# Eth-Crystal.net
KiCad netlist of a schematic drawn in Altium Designer
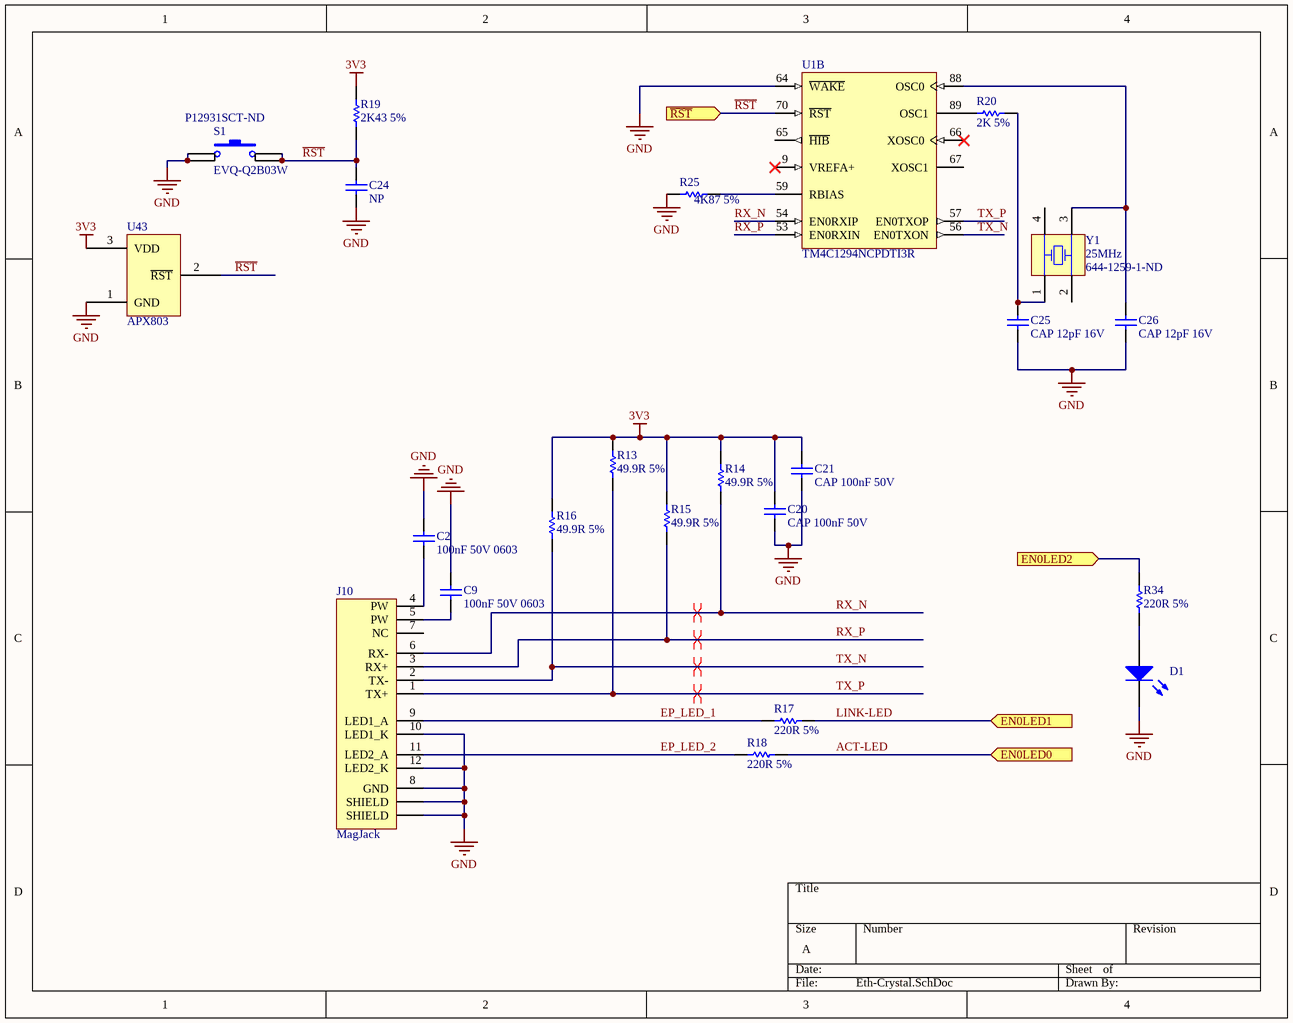
[diagram p0: Eth-Crystal.SchDoc]

(export (version "E")
  (design (tool "Eeschema 10.0.6"))
  (components
    (comp (ref "C2")
      (value "100nF 50V 0603")
      (footprint "CAPC0603(1608)100_M")
      (description "CAP 100nF 50V -20% to +80% 0603 (1608 Metric) Thickness 1mm SMD")
      (fields (field (name "TOLERANCE") "-20% to +80%"))
      (libsource (lib "Altium Content Vault") (part "CMP-1035-02594-1"))
    )
    (comp (ref "C9")
      (value "100nF 50V 0603")
      (footprint "CAPC0603(1608)100_M")
      (description "CAP 100nF 50V -20% to +80% 0603 (1608 Metric) Thickness 1mm SMD")
      (fields (field (name "TOLERANCE") "-20% to +80%"))
      (libsource (lib "Altium Content Vault") (part "CMP-1035-02594-1"))
    )
    (comp (ref "C20")
      (value "CAP 100nF 50V")
      (footprint "CAPC0603(1608)100_M")
      (description "CAP 100nF 50V Â±0.1pF 0603 (1608 Metric) Thickness 1mm SMD")
      (fields (field (name "TOLERANCE") "Â±0.1pF"))
      (libsource (lib "Altium Content Vault") (part "CMP-1035-00010-1"))
    )
    (comp (ref "C21")
      (value "CAP 100nF 50V")
      (footprint "CAPC0603(1608)100_M")
      (description "CAP 100nF 50V Â±0.1pF 0603 (1608 Metric) Thickness 1mm SMD")
      (fields (field (name "TOLERANCE") "Â±0.1pF"))
      (libsource (lib "Altium Content Vault") (part "CMP-1035-00010-1"))
    )
    (comp (ref "C24")
      (value "NP")
      (footprint "0603")
      (description "Capacitor (Semiconductor SIM Model)")
      (fields (field (name "PUBLISHER") "Altium Limited"))
      (libsource (lib "snarc+") (part "Cap_100pF"))
    )
    (comp (ref "C25")
      (value "CAP 12pF 16V")
      (footprint "CAPC0603(1608)100_L")
      (description "CAP 12pF 16V Â±0.25pF 0603 (1608 Metric) Thickness 1mm SMD")
      (fields (field (name "TOLERANCE") "Â±0.25pF"))
      (libsource (lib "Altium Content Vault") (part "CAP"))
    )
    (comp (ref "C26")
      (value "CAP 12pF 16V")
      (footprint "CAPC0603(1608)100_L")
      (description "CAP 12pF 16V Â±0.25pF 0603 (1608 Metric) Thickness 1mm SMD")
      (fields (field (name "TOLERANCE") "Â±0.25pF"))
      (libsource (lib "Altium Content Vault") (part "CAP"))
    )
    (comp (ref "D1")
      (value "LED")
      (footprint "LED-0603")
      (description "Typical RED, GREEN, YELLOW, AMBER GaAs LED")
      (fields (field (name "PUBLISHER") "Altium Limited"))
      (libsource (lib "HSBNE-Vend") (part "LED"))
    )
    (comp (ref "J10") (value "MagJack") (footprint "magjack") (libsource (lib "HSBNE-MAIN") (part "MagJack")))
    (comp (ref "R13")
      (value "49.9R 5%")
      (footprint "RESC0603(1608)_M")
      (description "49.9R 0.1W 5% 0603 (1608 Metric)  SMD")
      (fields (field (name "TOLERANCE") "5 %") (field (name "POWER") "0.1 W"))
      (libsource (lib "Altium Content Vault") (part "CMP-1012-00042-1"))
    )
    (comp (ref "R14")
      (value "49.9R 5%")
      (footprint "RESC0603(1608)_M")
      (description "49.9R 0.1W 5% 0603 (1608 Metric)  SMD")
      (fields (field (name "TOLERANCE") "5 %") (field (name "POWER") "0.1 W"))
      (libsource (lib "Altium Content Vault") (part "CMP-1012-00042-1"))
    )
    (comp (ref "R15")
      (value "49.9R 5%")
      (footprint "RESC0603(1608)_M")
      (description "49.9R 0.1W 5% 0603 (1608 Metric)  SMD")
      (fields (field (name "TOLERANCE") "5 %") (field (name "POWER") "0.1 W"))
      (libsource (lib "Altium Content Vault") (part "CMP-1012-00042-1"))
    )
    (comp (ref "R16")
      (value "49.9R 5%")
      (footprint "RESC0603(1608)_M")
      (description "49.9R 0.1W 5% 0603 (1608 Metric)  SMD")
      (fields (field (name "TOLERANCE") "5 %") (field (name "POWER") "0.1 W"))
      (libsource (lib "Altium Content Vault") (part "CMP-1012-00042-1"))
    )
    (comp (ref "R17")
      (value "220R 5%")
      (footprint "RESC0603(1608)_M")
      (description "220R 0.1W 5% 0603 (1608 Metric)  SMD")
      (fields (field (name "POWER") "0.1 W") (field (name "TOLERANCE") "5 %"))
      (libsource (lib "Altium Content Vault") (part "CMP-1012-00058-1"))
    )
    (comp (ref "R18")
      (value "220R 5%")
      (footprint "RESC0603(1608)_M")
      (description "220R 0.1W 5% 0603 (1608 Metric)  SMD")
      (fields (field (name "POWER") "0.1 W") (field (name "TOLERANCE") "5 %"))
      (libsource (lib "Altium Content Vault") (part "CMP-1012-00058-1"))
    )
    (comp (ref "R19")
      (value "2K43 5%")
      (footprint "RESC0603(1608)_M")
      (description "2K43 0.1W 5% 0603 (1608 Metric)  SMD")
      (fields (field (name "TOLERANCE") "5 %") (field (name "POWER") "0.1 W"))
      (libsource (lib "Altium Content Vault") (part "CMP-1012-00083-1"))
    )
    (comp (ref "R20")
      (value "2K 5%")
      (footprint "RESC0603(1608)_N")
      (description "2K 0.1W 5% 0603 (1608 Metric)  SMD")
      (fields (field (name "TOLERANCE") "5 %") (field (name "POWER") "0.1 W"))
      (libsource (lib "Altium Content Vault") (part "RES"))
    )
    (comp (ref "R25")
      (value "4K87 5%")
      (footprint "RESC0603(1608)_M")
      (description "4K87 0.1W 5% 0603 (1608 Metric)  SMD")
      (fields (field (name "TOLERANCE") "5 %") (field (name "POWER") "0.1 W"))
      (libsource (lib "Altium Content Vault") (part "CMP-1012-00090-1"))
    )
    (comp (ref "R34")
      (value "220R 5%")
      (footprint "RESC0603(1608)_M")
      (description "220R 0.1W 5% 0603 (1608 Metric)  SMD")
      (fields (field (name "POWER") "0.1 W") (field (name "TOLERANCE") "5 %"))
      (libsource (lib "Altium Content Vault") (part "CMP-1012-00058-1"))
    )
    (comp (ref "S1")
      (value "EVQ-Q2B03W")
      (footprint "TACTILE_SWITCH_SMD")
      (description "Switch")
      (fields
        (field (name "SUPPLIER PART NUMBER 1") "P12931SCT-ND")
        (field (name "PUBLISHER") "Altium Limited")
      )
      (libsource (lib "snarc+") (part "SW-PB"))
    )
    (comp (ref "U1")
      (value "TM4C1294NCPDTI3R")
      (footprint "TI-PDT128_M")
      (fields (field (name "MANUFACTURER") "Texas Instruments"))
      (libsource (lib "Altium Inc") (part "TI-TM4C1294NCPDT-128"))
    )
    (comp (ref "U43")
      (value "APX803")
      (footprint "SOT-23 - ESD")
      (description "IC MPU RESET CIRC 3.08V SOT23R-3")
      (libsource (lib "HSBNE-Vend") (part "APX803"))
    )
    (comp (ref "Y1")
      (value "25MHz")
      (footprint "Crystal 3.2x2.5")
      (description "Surface Mount Quartz Crystal")
      (fields
        (field (name "SUPPLIER PART NUMBER 1") "644-1259-1-ND")
        (field (name "PUBLISHER") "Altium Limited")
      )
      (libsource (lib "HSBNE-Vend") (part "Crystal_25MHz"))
    )
  )
  (nets
    (net (code "1") (name "/ACT-LED") (class "Default")
      (node (ref "R18") (pin "2") (pinfunction "2_2") (pintype "passive"))
    )
    (net (code "2") (name "/EN0LED2") (class "Default")
      (node (ref "R34") (pin "2") (pinfunction "2_2") (pintype "passive"))
    )
    (net (code "3") (name "/EP_LED_1") (class "Default")
      (node (ref "J10") (pin "9") (pinfunction "LED1_A_9") (pintype "passive"))
      (node (ref "R17") (pin "1") (pinfunction "1_1") (pintype "passive"))
    )
    (net (code "4") (name "/EP_LED_2") (class "Default")
      (node (ref "J10") (pin "11") (pinfunction "LED2_A_11") (pintype "passive"))
      (node (ref "R18") (pin "1") (pinfunction "1_1") (pintype "passive"))
    )
    (net (code "5") (name "/LINK-LED") (class "Default")
      (node (ref "R17") (pin "2") (pinfunction "2_2") (pintype "passive"))
    )
    (net (code "6") (name "/RX_N") (class "Default")
      (node (ref "J10") (pin "6") (pinfunction "RX-_6") (pintype "passive"))
      (node (ref "R14") (pin "1") (pinfunction "1_1") (pintype "passive"))
      (node (ref "U1") (pin "54") (pinfunction "EN0RXIP_54") (pintype "input"))
    )
    (net (code "7") (name "/RX_P") (class "Default")
      (node (ref "J10") (pin "3") (pinfunction "RX+_3") (pintype "passive"))
      (node (ref "R15") (pin "1") (pinfunction "1_1") (pintype "passive"))
      (node (ref "U1") (pin "53") (pinfunction "EN0RXIN_53") (pintype "input"))
    )
    (net (code "8") (name "/TX_N") (class "Default")
      (node (ref "J10") (pin "2") (pinfunction "TX-_2") (pintype "passive"))
      (node (ref "R16") (pin "1") (pinfunction "1_1") (pintype "passive"))
      (node (ref "U1") (pin "56") (pinfunction "EN0TXON_56") (pintype "output"))
    )
    (net (code "9") (name "/TX_P") (class "Default")
      (node (ref "J10") (pin "1") (pinfunction "TX+_1") (pintype "passive"))
      (node (ref "R13") (pin "1") (pinfunction "1_1") (pintype "passive"))
      (node (ref "U1") (pin "57") (pinfunction "EN0TXOP_57") (pintype "output"))
    )
    (net (code "10") (name "/~{RST}") (class "Default")
      (node (ref "C24") (pin "2") (pinfunction "2_2") (pintype "passive"))
      (node (ref "R19") (pin "1") (pinfunction "1_1") (pintype "passive"))
      (node (ref "S1") (pin "3") (pinfunction "3_3") (pintype "passive"))
      (node (ref "S1") (pin "4") (pinfunction "4_4") (pintype "passive"))
      (node (ref "U1") (pin "70") (pinfunction "~{RST}_70") (pintype "input"))
      (node (ref "U43") (pin "2") (pinfunction "~{RST}_2") (pintype "passive"))
    )
    (net (code "11") (name "3V3") (class "Default")
      (node (ref "C20") (pin "2") (pinfunction "2_2") (pintype "passive"))
      (node (ref "C21") (pin "2") (pinfunction "2_2") (pintype "passive"))
      (node (ref "R13") (pin "2") (pinfunction "2_2") (pintype "passive"))
      (node (ref "R14") (pin "2") (pinfunction "2_2") (pintype "passive"))
      (node (ref "R15") (pin "2") (pinfunction "2_2") (pintype "passive"))
      (node (ref "R16") (pin "2") (pinfunction "2_2") (pintype "passive"))
      (node (ref "R19") (pin "2") (pinfunction "2_2") (pintype "passive"))
      (node (ref "U43") (pin "3") (pinfunction "VDD_3") (pintype "passive"))
    )
    (net (code "12") (name "GND") (class "Default")
      (node (ref "C2") (pin "2") (pinfunction "2_2") (pintype "passive"))
      (node (ref "C20") (pin "1") (pinfunction "1_1") (pintype "passive"))
      (node (ref "C21") (pin "1") (pinfunction "1_1") (pintype "passive"))
      (node (ref "C24") (pin "1") (pinfunction "1_1") (pintype "passive"))
      (node (ref "C25") (pin "1") (pinfunction "1_1") (pintype "passive"))
      (node (ref "C26") (pin "1") (pinfunction "1_1") (pintype "passive"))
      (node (ref "C9") (pin "2") (pinfunction "2_2") (pintype "passive"))
      (node (ref "D1") (pin "2") (pinfunction "K_2") (pintype "passive"))
      (node (ref "J10") (pin "10") (pinfunction "LED1_K_10") (pintype "passive"))
      (node (ref "J10") (pin "12") (pinfunction "LED2_K_12") (pintype "passive"))
      (node (ref "J10") (pin "8") (pinfunction "GND_8") (pintype "passive"))
      (node (ref "J10") (pin "GND1") (pinfunction "SHIELD_GND1") (pintype "passive"))
      (node (ref "J10") (pin "GND2") (pinfunction "SHIELD_GND2") (pintype "passive"))
      (node (ref "R25") (pin "1") (pinfunction "1_1") (pintype "passive"))
      (node (ref "S1") (pin "1") (pinfunction "1_1") (pintype "passive"))
      (node (ref "S1") (pin "2") (pinfunction "2_2") (pintype "passive"))
      (node (ref "U1") (pin "64") (pinfunction "~{WAKE}_64") (pintype "input"))
      (node (ref "U43") (pin "1") (pinfunction "GND_1") (pintype "passive"))
    )
    (net (code "13") (name "Net-(C2-Pad1)") (class "Default")
      (node (ref "C2") (pin "1") (pinfunction "1_1") (pintype "passive"))
      (node (ref "J10") (pin "4") (pinfunction "PW_4") (pintype "passive"))
    )
    (net (code "14") (name "Net-(C9-Pad1)") (class "Default")
      (node (ref "C9") (pin "1") (pinfunction "1_1") (pintype "passive"))
      (node (ref "J10") (pin "5") (pinfunction "PW_5") (pintype "passive"))
    )
    (net (code "15") (name "Net-(C25-Pad2)") (class "Default")
      (node (ref "C25") (pin "2") (pinfunction "2_2") (pintype "passive"))
      (node (ref "R20") (pin "2") (pinfunction "2_2") (pintype "passive"))
      (node (ref "Y1") (pin "1") (pinfunction "OSC1_1") (pintype "passive"))
    )
    (net (code "16") (name "Net-(D1-A)") (class "Default")
      (node (ref "D1") (pin "1") (pinfunction "A_1") (pintype "passive"))
      (node (ref "R34") (pin "1") (pinfunction "1_1") (pintype "passive"))
    )
    (net (code "17") (name "Net-(U1B-OSC0)") (class "Default")
      (node (ref "C26") (pin "2") (pinfunction "2_2") (pintype "passive"))
      (node (ref "U1") (pin "88") (pinfunction "OSC0_88") (pintype "input"))
      (node (ref "Y1") (pin "3") (pinfunction "OSC2_3") (pintype "passive"))
    )
    (net (code "18") (name "Net-(U1B-OSC1)") (class "Default")
      (node (ref "R20") (pin "1") (pinfunction "1_1") (pintype "passive"))
      (node (ref "U1") (pin "89") (pinfunction "OSC1_89") (pintype "passive"))
    )
    (net (code "19") (name "Net-(U1B-RBIAS)") (class "Default")
      (node (ref "R25") (pin "2") (pinfunction "2_2") (pintype "passive"))
      (node (ref "U1") (pin "59") (pinfunction "RBIAS_59") (pintype "passive"))
    )
    (net (code "20") (name "unconnected-(J10-NC-Pad7)") (class "Default")
      (node (ref "J10") (pin "7") (pinfunction "NC_7") (pintype "passive"))
    )
    (net (code "21") (name "unconnected-(U1B-VREFA+-Pad9)") (class "Default")
      (node (ref "U1") (pin "9") (pinfunction "VREFA+_9") (pintype "input+no_connect"))
    )
    (net (code "22") (name "unconnected-(U1B-XOSC0-Pad66)") (class "Default")
      (node (ref "U1") (pin "66") (pinfunction "XOSC0_66") (pintype "input+no_connect"))
    )
    (net (code "23") (name "unconnected-(U1B-XOSC1-Pad67)") (class "Default")
      (node (ref "U1") (pin "67") (pinfunction "XOSC1_67") (pintype "passive"))
    )
    (net (code "24") (name "unconnected-(U1B-~{HIB}-Pad65)") (class "Default")
      (node (ref "U1") (pin "65") (pinfunction "~{HIB}_65") (pintype "output"))
    )
    (net (code "25") (name "unconnected-(Y1-OSC1-Pad4)") (class "Default")
      (node (ref "Y1") (pin "4") (pinfunction "OSC1_4") (pintype "passive"))
    )
    (net (code "26") (name "unconnected-(Y1-OSC2-Pad2)") (class "Default")
      (node (ref "Y1") (pin "2") (pinfunction "OSC2_2") (pintype "passive"))
    )
  )
)
